# MODELS.net
KiCad netlist of a schematic drawn in Altium Designer
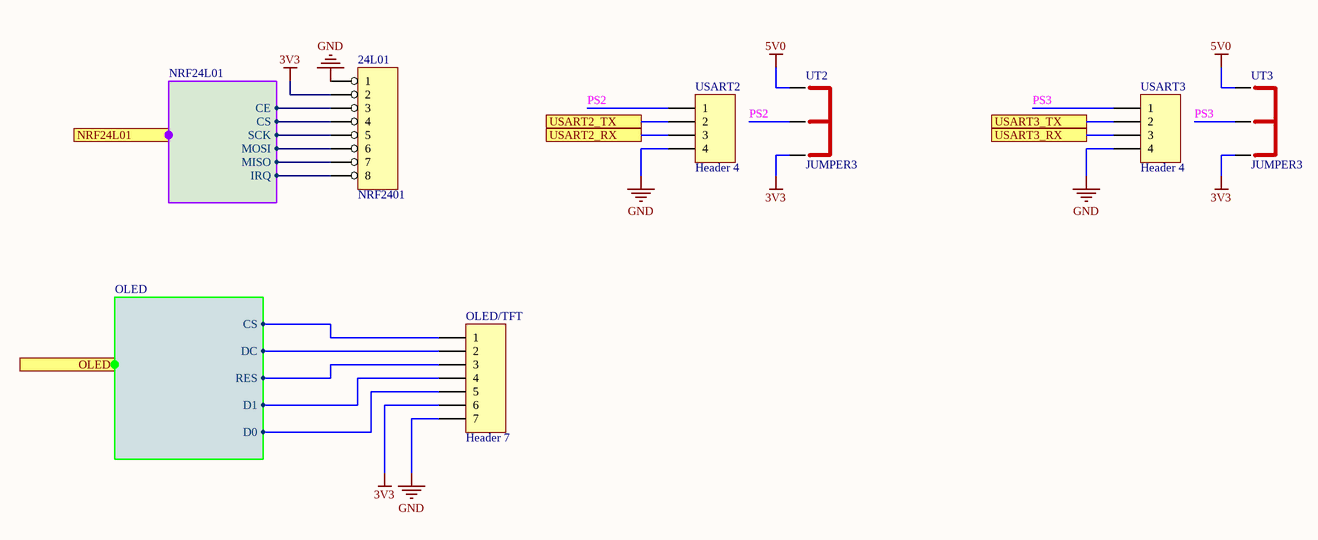
[diagram p0: MODELS.SchDoc]

(export (version "E")
  (design (tool "Eeschema 10.0.6"))
  (components
    (comp (ref "24L01")
      (value "NRF2401")
      (footprint "HDR2X4")
      (description "8 Pin Header")
      (libsource (lib "YT1_SCH_99SE") (part "HEADER 8"))
    )
    (comp (ref "OLED/TFT")
      (value "Header 7")
      (footprint "HDR1X7")
      (description "Header, 7-Pin")
      (fields (field (name "PUBLISHER") "Altium Limited"))
      (libsource (lib "Miscellaneous Connectors") (part "Header 7"))
    )
    (comp (ref "USART2")
      (value "Header 4")
      (footprint "HDR1X4")
      (description "Header, 4-Pin")
      (fields (field (name "PUBLISHER") "Altium Limited"))
      (libsource (lib "Miscellaneous Connectors") (part "Header 4"))
    )
    (comp (ref "USART3")
      (value "Header 4")
      (footprint "HDR1X4")
      (description "Header, 4-Pin")
      (fields (field (name "PUBLISHER") "Altium Limited"))
      (libsource (lib "Miscellaneous Connectors") (part "Header 4"))
    )
    (comp (ref "UT2")
      (value "JUMPER3")
      (footprint "Jumper3")
      (description "Jumper")
      (libsource (lib "LQ_Integrated_Library") (part "JUMPER3"))
    )
    (comp (ref "UT3")
      (value "JUMPER3")
      (footprint "Jumper3")
      (description "Jumper")
      (libsource (lib "LQ_Integrated_Library") (part "JUMPER3"))
    )
  )
  (nets
    (net (code "3") (name "/CE") (class "Default")
      (node (ref "24L01") (pin "3") (pinfunction "3_3") (pintype "passive"))
    )
    (net (code "4") (name "/D0") (class "Default")
      (node (ref "OLED/TFT") (pin "5") (pinfunction "5_5") (pintype "passive"))
    )
    (net (code "5") (name "/D1") (class "Default")
      (node (ref "OLED/TFT") (pin "4") (pinfunction "4_4") (pintype "passive"))
    )
    (net (code "6") (name "/DC") (class "Default")
      (node (ref "OLED/TFT") (pin "2") (pinfunction "2_2") (pintype "passive"))
    )
    (net (code "7") (name "/IRQ") (class "Default")
      (node (ref "24L01") (pin "8") (pinfunction "8_8") (pintype "passive"))
    )
    (net (code "8") (name "/MISO") (class "Default")
      (node (ref "24L01") (pin "7") (pinfunction "7_7") (pintype "passive"))
    )
    (net (code "9") (name "/MOSI") (class "Default")
      (node (ref "24L01") (pin "6") (pinfunction "6_6") (pintype "passive"))
    )
    (net (code "10") (name "/PS2") (class "Default")
      (node (ref "USART2") (pin "1") (pinfunction "1_1") (pintype "passive"))
      (node (ref "UT2") (pin "2") (pinfunction "2_2") (pintype "passive"))
    )
    (net (code "11") (name "/PS3") (class "Default")
      (node (ref "USART3") (pin "1") (pinfunction "1_1") (pintype "passive"))
      (node (ref "UT3") (pin "2") (pinfunction "2_2") (pintype "passive"))
    )
    (net (code "12") (name "/RES") (class "Default")
      (node (ref "OLED/TFT") (pin "3") (pinfunction "3_3") (pintype "passive"))
    )
    (net (code "13") (name "/SCK") (class "Default")
      (node (ref "24L01") (pin "5") (pinfunction "5_5") (pintype "passive"))
    )
    (net (code "14") (name "/USART2_RX") (class "Default")
      (node (ref "USART2") (pin "3") (pinfunction "3_3") (pintype "passive"))
    )
    (net (code "15") (name "/USART2_TX") (class "Default")
      (node (ref "USART2") (pin "2") (pinfunction "2_2") (pintype "passive"))
    )
    (net (code "16") (name "/USART3_RX") (class "Default")
      (node (ref "USART3") (pin "3") (pinfunction "3_3") (pintype "passive"))
    )
    (net (code "17") (name "/USART3_TX") (class "Default")
      (node (ref "USART3") (pin "2") (pinfunction "2_2") (pintype "passive"))
    )
    (net (code "20") (name "3V3") (class "Default")
      (node (ref "24L01") (pin "2") (pinfunction "2_2") (pintype "passive"))
      (node (ref "OLED/TFT") (pin "6") (pinfunction "6_6") (pintype "passive"))
      (node (ref "UT2") (pin "3") (pinfunction "3_3") (pintype "passive"))
      (node (ref "UT3") (pin "3") (pinfunction "3_3") (pintype "passive"))
    )
    (net (code "21") (name "5V0") (class "Default")
      (node (ref "UT2") (pin "1") (pinfunction "1_1") (pintype "passive"))
      (node (ref "UT3") (pin "1") (pinfunction "1_1") (pintype "passive"))
    )
    (net (code "22") (name "GND") (class "Default")
      (node (ref "24L01") (pin "1") (pinfunction "1_1") (pintype "passive"))
      (node (ref "OLED/TFT") (pin "7") (pinfunction "7_7") (pintype "passive"))
      (node (ref "USART2") (pin "4") (pinfunction "4_4") (pintype "passive"))
      (node (ref "USART3") (pin "4") (pinfunction "4_4") (pintype "passive"))
    )
    (net (code "23") (name "unconnected-(24L01-Pad4)") (class "Default")
      (node (ref "24L01") (pin "4") (pinfunction "4_4") (pintype "passive"))
    )
    (net (code "24") (name "unconnected-(OLED/TFT-Pad1)") (class "Default")
      (node (ref "OLED/TFT") (pin "1") (pinfunction "1_1") (pintype "passive"))
    )
  )
)
